# GenesysHat_-_System.net
KiCad netlist of a schematic drawn in Altium Designer
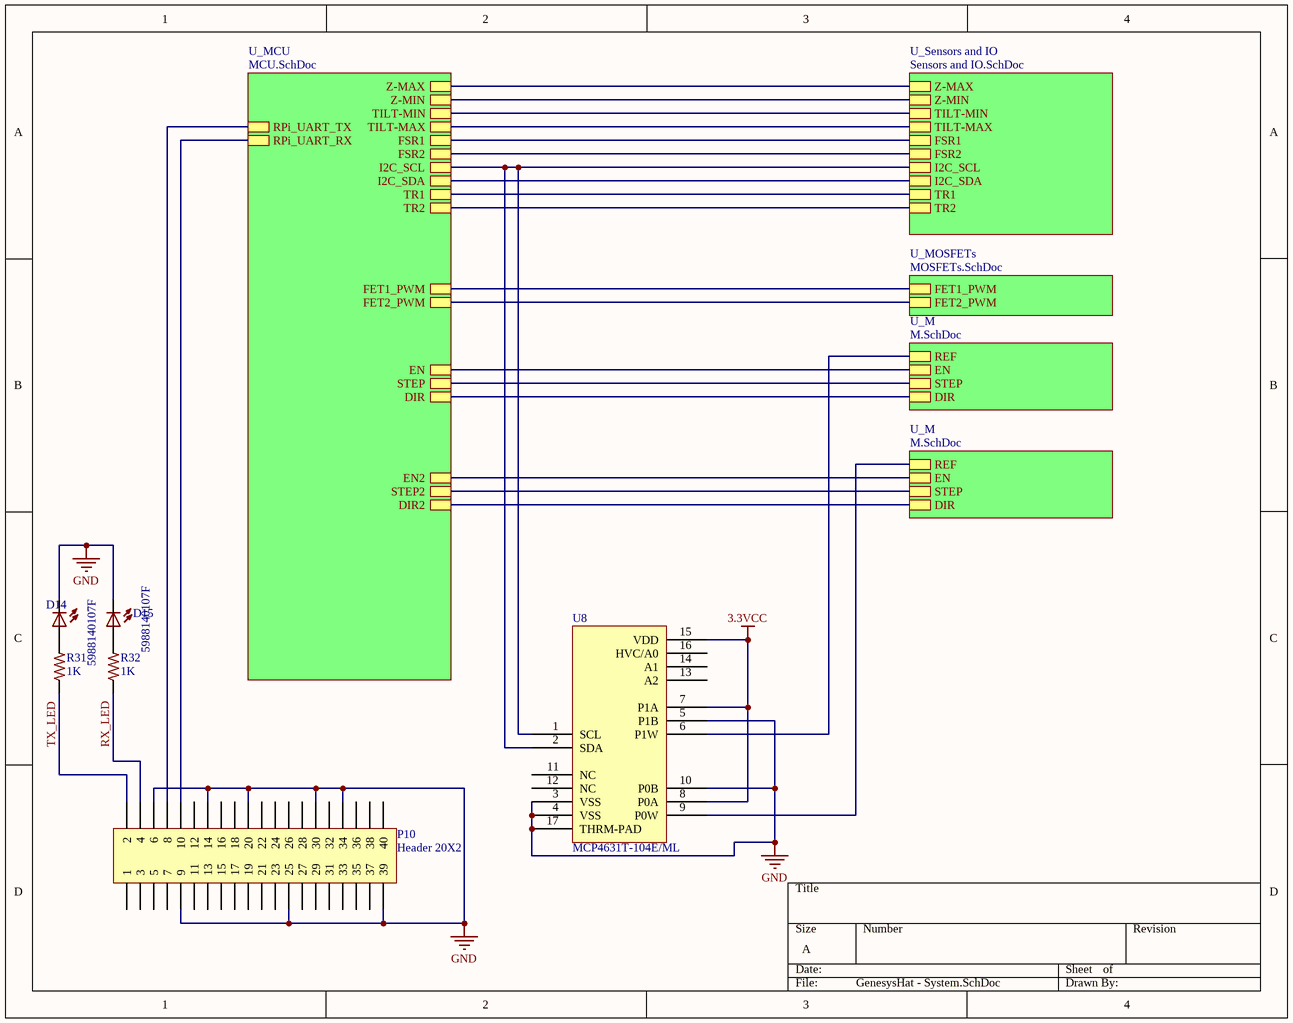
[diagram p0: GenesysHat - System.SchDoc]

(export (version "E")
  (design (tool "Eeschema 10.0.6"))
  (components
    (comp (ref "D14")
      (value "5988140107F")
      (footprint "LED2012120")
      (description "LED 0805 Yellow")
      (fields (field (name "PUBLISHER") "UltiMachine"))
      (libsource (lib "Tigershark3D") (part "5988140107F"))
    )
    (comp (ref "D15")
      (value "5988140107F")
      (footprint "LED2012120")
      (description "LED 0805 Yellow")
      (fields (field (name "PUBLISHER") "UltiMachine"))
      (libsource (lib "Tigershark3D") (part "5988140107F"))
    )
    (comp (ref "P10")
      (value "Header 20X2")
      (footprint "HDR2X20")
      (description "Header, 20-Pin, Dual row")
      (fields (field (name "PUBLISHER") "Altium Limited"))
      (libsource (lib "Miscellaneous Connectors") (part "Header 20X2"))
    )
    (comp (ref "R31")
      (value "1K")
      (footprint "R0603")
      (description "RES 0603 1K 100mW 1%")
      (fields
        (field (name "MANUFACTURERPARTNUMBER") "ERJ-3EKF1001V")
        (field (name "PUBLISHER") "UltiMachine")
      )
      (libsource (lib "Tigershark3D") (part "ERJ-3EKF1001V"))
    )
    (comp (ref "R32")
      (value "1K")
      (footprint "R0603")
      (description "RES 0603 1K 100mW 1%")
      (fields
        (field (name "MANUFACTURERPARTNUMBER") "ERJ-3EKF1001V")
        (field (name "PUBLISHER") "UltiMachine")
      )
      (libsource (lib "Tigershark3D") (part "ERJ-3EKF1001V"))
    )
    (comp (ref "U8")
      (value "MCP4631T-104E/ML")
      (footprint "MCP4631T-104E/ML")
      (description "IC DGTL POT 100K 129TAPS 16-QF")
      (fields (field (name "MFR") "Microchip"))
      (libsource (lib "GenesysHat") (part "MCP4631T-104E/ML"))
    )
  )
  (nets
    (net (code "9") (name "/I2C_SCL") (class "Default")
      (node (ref "U8") (pin "1") (pinfunction "SCL_1") (pintype "passive"))
      (node (ref "U8") (pin "2") (pinfunction "SDA_2") (pintype "passive"))
    )
    (net (code "11") (name "/REF") (class "Default")
      (node (ref "U8") (pin "6") (pinfunction "P1W_6") (pintype "passive"))
    )
    (net (code "12") (name "/REF_1") (class "Default")
      (node (ref "U8") (pin "9") (pinfunction "P0W_9") (pintype "passive"))
    )
    (net (code "13") (name "/RPi_UART_RX") (class "Default")
      (node (ref "P10") (pin "10") (pinfunction "10_10") (pintype "passive"))
    )
    (net (code "14") (name "/RPi_UART_TX") (class "Default")
      (node (ref "P10") (pin "8") (pinfunction "8_8") (pintype "passive"))
    )
    (net (code "15") (name "/RX_LED") (class "Default")
      (node (ref "P10") (pin "4") (pinfunction "4_4") (pintype "passive"))
      (node (ref "R32") (pin "1") (pinfunction "1_1") (pintype "passive"))
    )
    (net (code "22") (name "/TX_LED") (class "Default")
      (node (ref "P10") (pin "2") (pinfunction "2_2") (pintype "passive"))
      (node (ref "R31") (pin "1") (pinfunction "1_1") (pintype "passive"))
    )
    (net (code "25") (name "3.3VCC") (class "Default")
      (node (ref "U8") (pin "15") (pinfunction "VDD_15") (pintype "passive"))
      (node (ref "U8") (pin "7") (pinfunction "P1A_7") (pintype "passive"))
      (node (ref "U8") (pin "8") (pinfunction "P0A_8") (pintype "passive"))
    )
    (net (code "26") (name "GND") (class "Default")
      (node (ref "D14") (pin "C") (pinfunction "C_C") (pintype "passive"))
      (node (ref "D15") (pin "C") (pinfunction "C_C") (pintype "passive"))
      (node (ref "P10") (pin "14") (pinfunction "14_14") (pintype "passive"))
      (node (ref "P10") (pin "20") (pinfunction "20_20") (pintype "passive"))
      (node (ref "P10") (pin "25") (pinfunction "25_25") (pintype "passive"))
      (node (ref "P10") (pin "30") (pinfunction "30_30") (pintype "passive"))
      (node (ref "P10") (pin "34") (pinfunction "34_34") (pintype "passive"))
      (node (ref "P10") (pin "39") (pinfunction "39_39") (pintype "passive"))
      (node (ref "P10") (pin "6") (pinfunction "6_6") (pintype "passive"))
      (node (ref "P10") (pin "9") (pinfunction "9_9") (pintype "passive"))
      (node (ref "U8") (pin "10") (pinfunction "P0B_10") (pintype "passive"))
      (node (ref "U8") (pin "17") (pinfunction "THRM-PAD_17") (pintype "passive"))
      (node (ref "U8") (pin "3") (pinfunction "VSS_3") (pintype "passive"))
      (node (ref "U8") (pin "4") (pinfunction "VSS_4") (pintype "passive"))
      (node (ref "U8") (pin "5") (pinfunction "P1B_5") (pintype "passive"))
    )
    (net (code "27") (name "Net-(D14-PadA)") (class "Default")
      (node (ref "D14") (pin "A") (pinfunction "A_A") (pintype "passive"))
      (node (ref "R31") (pin "2") (pinfunction "2_2") (pintype "passive"))
    )
    (net (code "28") (name "Net-(D15-PadA)") (class "Default")
      (node (ref "D15") (pin "A") (pinfunction "A_A") (pintype "passive"))
      (node (ref "R32") (pin "2") (pinfunction "2_2") (pintype "passive"))
    )
    (net (code "29") (name "unconnected-(P10-Pad1)") (class "Default")
      (node (ref "P10") (pin "1") (pinfunction "1_1") (pintype "passive"))
    )
    (net (code "30") (name "unconnected-(P10-Pad3)") (class "Default")
      (node (ref "P10") (pin "3") (pinfunction "3_3") (pintype "passive"))
    )
    (net (code "31") (name "unconnected-(P10-Pad5)") (class "Default")
      (node (ref "P10") (pin "5") (pinfunction "5_5") (pintype "passive"))
    )
    (net (code "32") (name "unconnected-(P10-Pad7)") (class "Default")
      (node (ref "P10") (pin "7") (pinfunction "7_7") (pintype "passive"))
    )
    (net (code "33") (name "unconnected-(P10-Pad11)") (class "Default")
      (node (ref "P10") (pin "11") (pinfunction "11_11") (pintype "passive"))
    )
    (net (code "34") (name "unconnected-(P10-Pad12)") (class "Default")
      (node (ref "P10") (pin "12") (pinfunction "12_12") (pintype "passive"))
    )
    (net (code "35") (name "unconnected-(P10-Pad13)") (class "Default")
      (node (ref "P10") (pin "13") (pinfunction "13_13") (pintype "passive"))
    )
    (net (code "36") (name "unconnected-(P10-Pad15)") (class "Default")
      (node (ref "P10") (pin "15") (pinfunction "15_15") (pintype "passive"))
    )
    (net (code "37") (name "unconnected-(P10-Pad16)") (class "Default")
      (node (ref "P10") (pin "16") (pinfunction "16_16") (pintype "passive"))
    )
    (net (code "38") (name "unconnected-(P10-Pad17)") (class "Default")
      (node (ref "P10") (pin "17") (pinfunction "17_17") (pintype "passive"))
    )
    (net (code "39") (name "unconnected-(P10-Pad18)") (class "Default")
      (node (ref "P10") (pin "18") (pinfunction "18_18") (pintype "passive"))
    )
    (net (code "40") (name "unconnected-(P10-Pad19)") (class "Default")
      (node (ref "P10") (pin "19") (pinfunction "19_19") (pintype "passive"))
    )
    (net (code "41") (name "unconnected-(P10-Pad21)") (class "Default")
      (node (ref "P10") (pin "21") (pinfunction "21_21") (pintype "passive"))
    )
    (net (code "42") (name "unconnected-(P10-Pad22)") (class "Default")
      (node (ref "P10") (pin "22") (pinfunction "22_22") (pintype "passive"))
    )
    (net (code "43") (name "unconnected-(P10-Pad23)") (class "Default")
      (node (ref "P10") (pin "23") (pinfunction "23_23") (pintype "passive"))
    )
    (net (code "44") (name "unconnected-(P10-Pad24)") (class "Default")
      (node (ref "P10") (pin "24") (pinfunction "24_24") (pintype "passive"))
    )
    (net (code "45") (name "unconnected-(P10-Pad26)") (class "Default")
      (node (ref "P10") (pin "26") (pinfunction "26_26") (pintype "passive"))
    )
    (net (code "46") (name "unconnected-(P10-Pad27)") (class "Default")
      (node (ref "P10") (pin "27") (pinfunction "27_27") (pintype "passive"))
    )
    (net (code "47") (name "unconnected-(P10-Pad28)") (class "Default")
      (node (ref "P10") (pin "28") (pinfunction "28_28") (pintype "passive"))
    )
    (net (code "48") (name "unconnected-(P10-Pad29)") (class "Default")
      (node (ref "P10") (pin "29") (pinfunction "29_29") (pintype "passive"))
    )
    (net (code "49") (name "unconnected-(P10-Pad31)") (class "Default")
      (node (ref "P10") (pin "31") (pinfunction "31_31") (pintype "passive"))
    )
    (net (code "50") (name "unconnected-(P10-Pad32)") (class "Default")
      (node (ref "P10") (pin "32") (pinfunction "32_32") (pintype "passive"))
    )
    (net (code "51") (name "unconnected-(P10-Pad33)") (class "Default")
      (node (ref "P10") (pin "33") (pinfunction "33_33") (pintype "passive"))
    )
    (net (code "52") (name "unconnected-(P10-Pad35)") (class "Default")
      (node (ref "P10") (pin "35") (pinfunction "35_35") (pintype "passive"))
    )
    (net (code "53") (name "unconnected-(P10-Pad36)") (class "Default")
      (node (ref "P10") (pin "36") (pinfunction "36_36") (pintype "passive"))
    )
    (net (code "54") (name "unconnected-(P10-Pad37)") (class "Default")
      (node (ref "P10") (pin "37") (pinfunction "37_37") (pintype "passive"))
    )
    (net (code "55") (name "unconnected-(P10-Pad38)") (class "Default")
      (node (ref "P10") (pin "38") (pinfunction "38_38") (pintype "passive"))
    )
    (net (code "56") (name "unconnected-(P10-Pad40)") (class "Default")
      (node (ref "P10") (pin "40") (pinfunction "40_40") (pintype "passive"))
    )
    (net (code "57") (name "unconnected-(U8-A1-Pad14)") (class "Default")
      (node (ref "U8") (pin "14") (pinfunction "A1_14") (pintype "passive"))
    )
    (net (code "58") (name "unconnected-(U8-A2-Pad13)") (class "Default")
      (node (ref "U8") (pin "13") (pinfunction "A2_13") (pintype "passive"))
    )
    (net (code "59") (name "unconnected-(U8-HVC{slash}A0-Pad16)") (class "Default")
      (node (ref "U8") (pin "16") (pinfunction "HVC/A0_16") (pintype "passive"))
    )
    (net (code "60") (name "unconnected-(U8-NC-Pad11)") (class "Default")
      (node (ref "U8") (pin "11") (pinfunction "NC_11") (pintype "passive"))
    )
    (net (code "61") (name "unconnected-(U8-NC-Pad12)") (class "Default")
      (node (ref "U8") (pin "12") (pinfunction "NC_12") (pintype "passive"))
    )
  )
)
